# piezo-preamp-tickler_V0-7.net
KiCad netlist of a schematic drawn in EAGLE
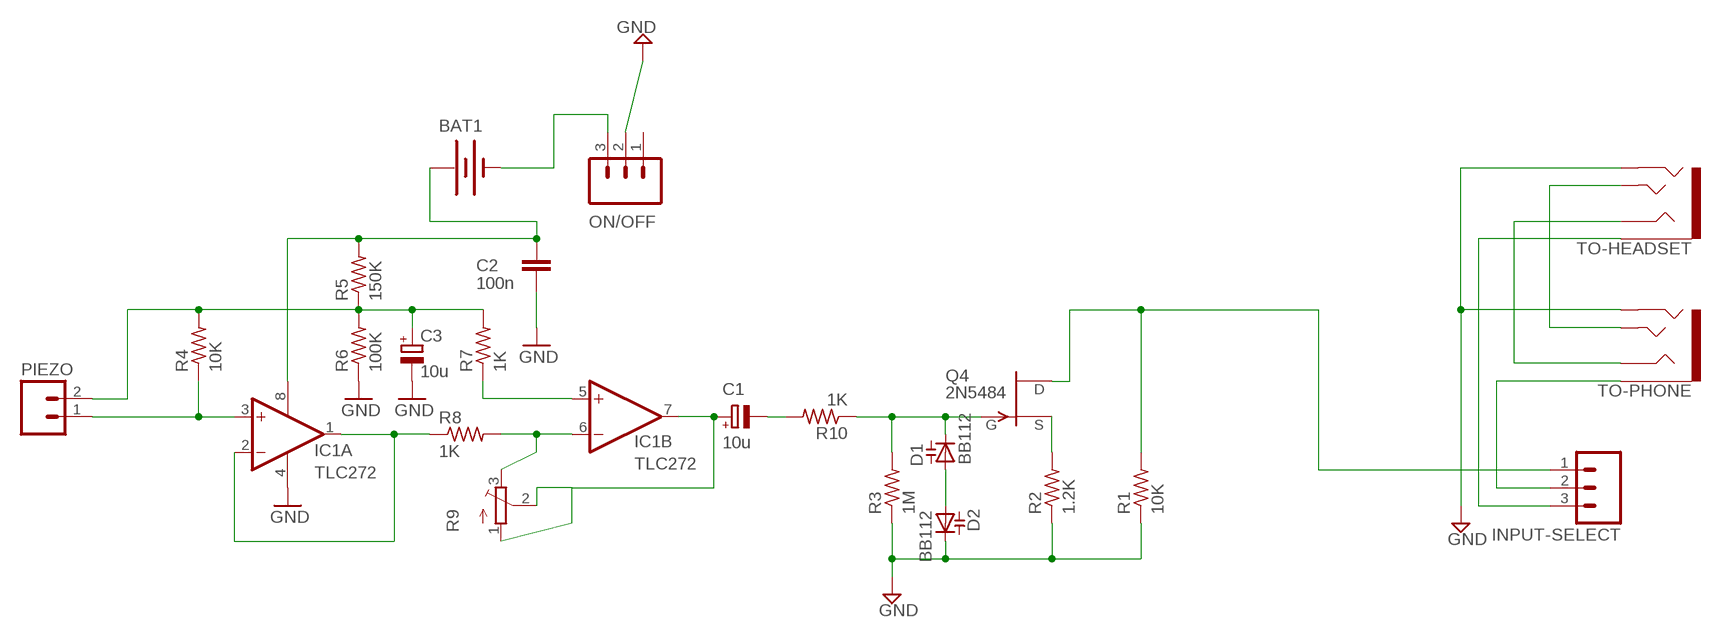
[diagram p0: schematic, sheet 1]

(export (version "E")
  (design (tool "Eeschema 10.0.6"))
  (components
    (comp (ref "BAT1")
      (value "BATTERYA23")
      (footprint "eagle-import:BATTERY-A23")
      (libsource (lib "eagle-import") (part "BATTERYA23"))
    )
    (comp (ref "C1")
      (value "10u")
      (footprint "eagle-import:E2,5-5")
      (libsource (lib "eagle-import") (part "CPOL-EUE2.5-5"))
    )
    (comp (ref "C2")
      (value "100n")
      (footprint "eagle-import:C025-025X050")
      (libsource (lib "eagle-import") (part "C-EU025-025X050"))
    )
    (comp (ref "C3")
      (value "10u")
      (footprint "eagle-import:E2,5-5")
      (libsource (lib "eagle-import") (part "CPOL-EUE2.5-5"))
    )
    (comp (ref "D1")
      (value "BB112")
      (footprint "eagle-import:SOT54H")
      (libsource (lib "eagle-import") (part "BB112"))
    )
    (comp (ref "D2")
      (value "BB112")
      (footprint "eagle-import:SOT54H")
      (libsource (lib "eagle-import") (part "BB112"))
    )
    (comp (ref "IC1")
      (value "TLC272")
      (footprint "eagle-import:DIL08")
      (libsource (lib "eagle-import") (part "TLC272P"))
    )
    (comp (ref "INPUT-SELECT")
      (value "M03SINGLE-POLE-DOUBLE-THROW")
      (footprint "eagle-import:SPDT-SWITCH")
      (libsource (lib "eagle-import") (part "M03SINGLE-POLE-DOUBLE-THROW"))
    )
    (comp (ref "ON/OFF")
      (value "labl")
      (footprint "eagle-import:SPDT-SWITCH")
      (libsource (lib "eagle-import") (part "M03SINGLE-POLE-DOUBLE-THROW"))
    )
    (comp (ref "PIEZO")
      (value "M02LOCK")
      (footprint "eagle-import:1X02_LOCK")
      (libsource (lib "eagle-import") (part "M02LOCK"))
    )
    (comp (ref "Q4")
      (value "2N5484")
      (footprint "eagle-import:TO92-")
      (libsource (lib "eagle-import") (part "?5482N4"))
    )
    (comp (ref "R1")
      (value "10K")
      (footprint "eagle-import:0204V")
      (libsource (lib "eagle-import") (part "R-US_0204/2V"))
    )
    (comp (ref "R2")
      (value "1.2K")
      (footprint "eagle-import:0204V")
      (libsource (lib "eagle-import") (part "R-US_0204/2V"))
    )
    (comp (ref "R3")
      (value "1M")
      (footprint "eagle-import:0204V")
      (libsource (lib "eagle-import") (part "R-US_0204/2V"))
    )
    (comp (ref "R4")
      (value "10K")
      (footprint "eagle-import:0204V")
      (libsource (lib "eagle-import") (part "R-US_0204/2V"))
    )
    (comp (ref "R5")
      (value "150K")
      (footprint "eagle-import:0204V")
      (libsource (lib "eagle-import") (part "R-US_0204/2V"))
    )
    (comp (ref "R6")
      (value "100K")
      (footprint "eagle-import:0204V")
      (libsource (lib "eagle-import") (part "R-US_0204/2V"))
    )
    (comp (ref "R7")
      (value "1K")
      (footprint "eagle-import:0204V")
      (libsource (lib "eagle-import") (part "R-US_0204/2V"))
    )
    (comp (ref "R8")
      (value "1K")
      (footprint "eagle-import:0204V")
      (libsource (lib "eagle-import") (part "R-US_0204/2V"))
    )
    (comp (ref "R9")
      (value "TRIMPOT3386")
      (footprint "eagle-import:TRIM-3386")
      (libsource (lib "eagle-import") (part "TRIMPOT3386"))
    )
    (comp (ref "R10")
      (value "1K")
      (footprint "eagle-import:0204V")
      (libsource (lib "eagle-import") (part "R-US_0204/2V"))
    )
    (comp (ref "TO-HEADSET")
      (value "AUDIO-JACK3")
      (footprint "eagle-import:AUDIO-JACK-TRRS-SMD")
      (libsource (lib "eagle-import") (part "AUDIO-JACK3"))
    )
    (comp (ref "TO-PHONE")
      (value "AUDIO-JACK3")
      (footprint "eagle-import:AUDIO-JACK-TRRS-SMD")
      (libsource (lib "eagle-import") (part "AUDIO-JACK3"))
    )
  )
  (nets
    (net (code "1") (name "GND") (class "Default")
      (node (ref "C2") (pin "1") (pinfunction "1_1") (pintype "passive"))
      (node (ref "C3") (pin "-") (pinfunction "-_-") (pintype "passive"))
      (node (ref "D2") (pin "C") (pinfunction "C_C") (pintype "passive"))
      (node (ref "IC1") (pin "4") (pinfunction "V-_4") (pintype "power_in"))
      (node (ref "ON/OFF") (pin "2") (pinfunction "2_2") (pintype "passive"))
      (node (ref "R1") (pin "1") (pinfunction "1_1") (pintype "passive"))
      (node (ref "R2") (pin "1") (pinfunction "1_1") (pintype "passive"))
      (node (ref "R3") (pin "1") (pinfunction "1_1") (pintype "passive"))
      (node (ref "R6") (pin "1") (pinfunction "1_1") (pintype "passive"))
      (node (ref "TO-HEADSET") (pin "RING2") (pinfunction "RING2_RING2") (pintype "bidirectional"))
      (node (ref "TO-PHONE") (pin "RING2") (pinfunction "RING2_RING2") (pintype "bidirectional"))
    )
    (net (code "2") (name "Net-(BAT1-+)") (class "Default")
      (node (ref "BAT1") (pin "PWR@1") (pinfunction "+_PWR@1") (pintype "power_in"))
      (node (ref "C2") (pin "2") (pinfunction "2_2") (pintype "passive"))
      (node (ref "IC1") (pin "8") (pinfunction "V+_8") (pintype "power_in"))
      (node (ref "R5") (pin "2") (pinfunction "2_2") (pintype "passive"))
    )
    (net (code "3") (name "Net-(BAT1--)") (class "Default")
      (node (ref "BAT1") (pin "GND@1") (pinfunction "-_GND@1") (pintype "power_in"))
      (node (ref "ON/OFF") (pin "3") (pinfunction "3_3") (pintype "passive"))
    )
    (net (code "4") (name "Net-(C1-Pad-)") (class "Default")
      (node (ref "C1") (pin "-") (pinfunction "-_-") (pintype "passive"))
      (node (ref "R10") (pin "2") (pinfunction "2_2") (pintype "passive"))
    )
    (net (code "5") (name "Net-(C3-Pad+)") (class "Default")
      (node (ref "C3") (pin "+") (pinfunction "+_+") (pintype "passive"))
      (node (ref "PIEZO") (pin "2") (pinfunction "2_2") (pintype "passive"))
      (node (ref "R4") (pin "2") (pinfunction "2_2") (pintype "passive"))
      (node (ref "R5") (pin "1") (pinfunction "1_1") (pintype "passive"))
      (node (ref "R6") (pin "2") (pinfunction "2_2") (pintype "passive"))
      (node (ref "R7") (pin "2") (pinfunction "2_2") (pintype "passive"))
    )
    (net (code "6") (name "Net-(D1-PadA)") (class "Default")
      (node (ref "D1") (pin "A") (pinfunction "A_A") (pintype "passive"))
      (node (ref "D2") (pin "A") (pinfunction "A_A") (pintype "passive"))
    )
    (net (code "7") (name "Net-(IC1A-+IN)") (class "Default")
      (node (ref "IC1") (pin "3") (pinfunction "+IN_3") (pintype "input"))
      (node (ref "PIEZO") (pin "1") (pinfunction "1_1") (pintype "passive"))
      (node (ref "R4") (pin "1") (pinfunction "1_1") (pintype "passive"))
    )
    (net (code "8") (name "Net-(IC1A--IN)") (class "Default")
      (node (ref "IC1") (pin "1") (pinfunction "OUT_1") (pintype "output"))
      (node (ref "IC1") (pin "2") (pinfunction "-IN_2") (pintype "input"))
      (node (ref "R8") (pin "1") (pinfunction "1_1") (pintype "passive"))
    )
    (net (code "9") (name "Net-(IC1B-+IN)") (class "Default")
      (node (ref "IC1") (pin "5") (pinfunction "+IN_5") (pintype "input"))
      (node (ref "R7") (pin "1") (pinfunction "1_1") (pintype "passive"))
    )
    (net (code "10") (name "Net-(IC1B--IN)") (class "Default")
      (node (ref "IC1") (pin "6") (pinfunction "-IN_6") (pintype "input"))
      (node (ref "R8") (pin "2") (pinfunction "2_2") (pintype "passive"))
      (node (ref "R9") (pin "3") (pinfunction "E_3") (pintype "passive"))
    )
    (net (code "11") (name "Net-(IC1B-OUT)") (class "Default")
      (node (ref "C1") (pin "+") (pinfunction "+_+") (pintype "passive"))
      (node (ref "IC1") (pin "7") (pinfunction "OUT_7") (pintype "output"))
      (node (ref "R9") (pin "1") (pinfunction "A_1") (pintype "passive"))
      (node (ref "R9") (pin "2") (pinfunction "S_2") (pintype "passive"))
    )
    (net (code "12") (name "Net-(INPUT-SELECT-Pad2)") (class "Default")
      (node (ref "INPUT-SELECT") (pin "2") (pinfunction "2_2") (pintype "passive"))
      (node (ref "TO-PHONE") (pin "EARTH") (pinfunction "EARTH_EARTH") (pintype "bidirectional"))
    )
    (net (code "13") (name "Net-(INPUT-SELECT-Pad3)") (class "Default")
      (node (ref "INPUT-SELECT") (pin "3") (pinfunction "3_3") (pintype "passive"))
      (node (ref "TO-HEADSET") (pin "EARTH") (pinfunction "EARTH_EARTH") (pintype "bidirectional"))
    )
    (net (code "14") (name "Net-(Q4-D)") (class "Default")
      (node (ref "INPUT-SELECT") (pin "1") (pinfunction "1_1") (pintype "passive"))
      (node (ref "Q4") (pin "3") (pinfunction "D_3") (pintype "passive"))
      (node (ref "R1") (pin "2") (pinfunction "2_2") (pintype "passive"))
    )
    (net (code "15") (name "Net-(Q4-G)") (class "Default")
      (node (ref "D1") (pin "C") (pinfunction "C_C") (pintype "passive"))
      (node (ref "Q4") (pin "1") (pinfunction "G_1") (pintype "passive"))
      (node (ref "R10") (pin "1") (pinfunction "1_1") (pintype "passive"))
      (node (ref "R3") (pin "2") (pinfunction "2_2") (pintype "passive"))
    )
    (net (code "16") (name "Net-(Q4-S)") (class "Default")
      (node (ref "Q4") (pin "2") (pinfunction "S_2") (pintype "passive"))
      (node (ref "R2") (pin "2") (pinfunction "2_2") (pintype "passive"))
    )
    (net (code "17") (name "Net-(TO-HEADSET-PadRING1)") (class "Default")
      (node (ref "TO-HEADSET") (pin "RING1") (pinfunction "RING1_RING1") (pintype "bidirectional"))
      (node (ref "TO-PHONE") (pin "RING1") (pinfunction "RING1_RING1") (pintype "bidirectional"))
    )
    (net (code "18") (name "Net-(TO-HEADSET-PadTIP)") (class "Default")
      (node (ref "TO-HEADSET") (pin "TIP") (pinfunction "TIP_TIP") (pintype "bidirectional"))
      (node (ref "TO-PHONE") (pin "TIP") (pinfunction "TIP_TIP") (pintype "bidirectional"))
    )
    (net (code "19") (name "unconnected-(ON/OFF-Pad1)") (class "Default")
      (node (ref "ON/OFF") (pin "1") (pinfunction "1_1") (pintype "passive"))
    )
  )
)
